# Schematic.net
KiCad netlist of a schematic drawn in Altium Designer
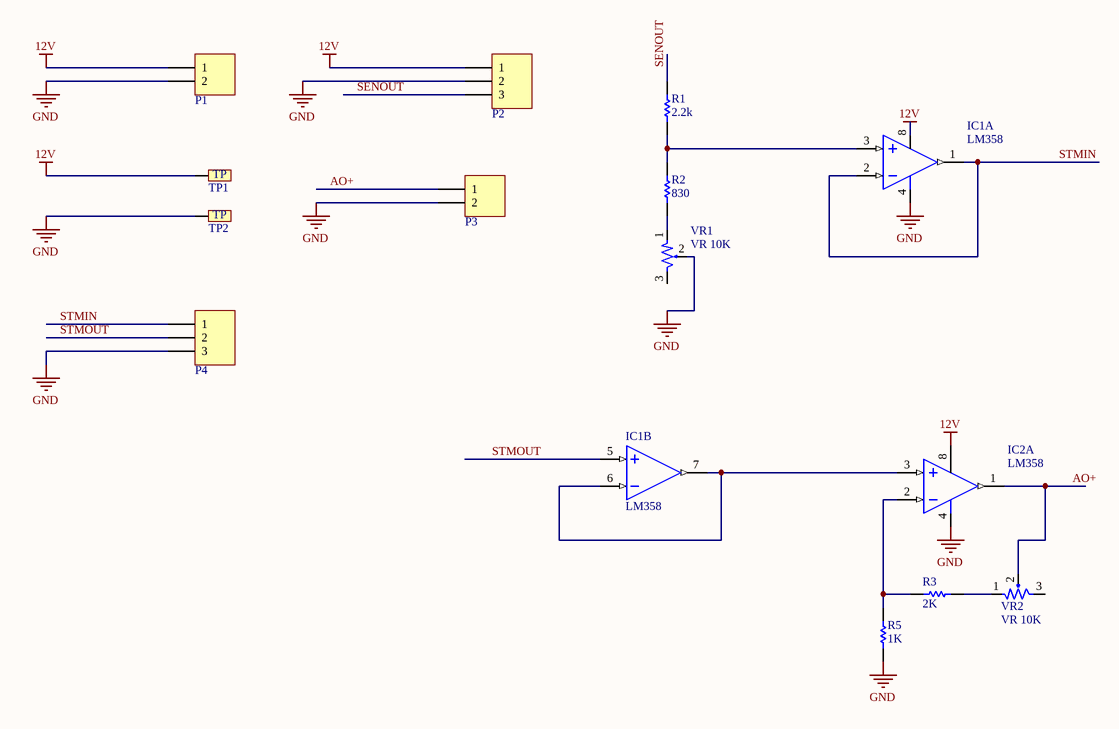
[diagram p0: Schematic.SchDoc]

(export (version "E")
  (design (tool "Eeschema 10.0.6"))
  (components
    (comp (ref "IC1")
      (value "LM358")
      (footprint "DIP8")
      (description "Low-Power Dual Operational Amplifier")
      (libsource (lib "LIBRARY") (part "LM358"))
    )
    (comp (ref "IC2")
      (value "LM358")
      (footprint "DIP8")
      (description "Low-Power Dual Operational Amplifier")
      (libsource (lib "LIBRARY") (part "LM358"))
    )
    (comp (ref "P1")
      (value "Header 2H")
      (footprint "JP2H")
      (description "Header, 2-Pin, Right Angle")
      (fields (field (name "PUBLISHER") "Altium Limited"))
      (libsource (lib "PIF_Library") (part "Header 2H"))
    )
    (comp (ref "P2")
      (value "Header 3")
      (footprint "JP3")
      (description "Header, 3-Pin")
      (fields (field (name "PUBLISHER") "Altium Limited"))
      (libsource (lib "PIF_Library") (part "Header 3"))
    )
    (comp (ref "P3")
      (value "Header 2H")
      (footprint "JP2H")
      (description "Header, 2-Pin, Right Angle")
      (fields (field (name "PUBLISHER") "Altium Limited"))
      (libsource (lib "PIF_Library") (part "Header 2H"))
    )
    (comp (ref "P4")
      (value "Header 3")
      (footprint "JP3")
      (description "Header, 3-Pin")
      (fields (field (name "PUBLISHER") "Altium Limited"))
      (libsource (lib "PIF_Library") (part "Header 3"))
    )
    (comp (ref "R1")
      (value "2.2k")
      (footprint "RES-SM-0805")
      (description "Resistor")
      (fields (field (name "Comment") "RESISTOR SMD"))
      (libsource (lib "PIF_Library") (part "RESISTOR SMD"))
    )
    (comp (ref "R2")
      (value "830")
      (footprint "RES-SM-0805")
      (description "Resistor")
      (fields (field (name "Comment") "RESISTOR SMD"))
      (libsource (lib "PIF_Library") (part "RESISTOR SMD"))
    )
    (comp (ref "R3")
      (value "2K")
      (footprint "RES-SM-0805")
      (description "Resistor")
      (fields (field (name "Comment") "RESISTOR SMD"))
      (libsource (lib "PIF_Library") (part "RESISTOR SMD"))
    )
    (comp (ref "R5")
      (value "1K")
      (footprint "RES-SM-0805")
      (description "Resistor")
      (fields (field (name "Comment") "RESISTOR SMD"))
      (libsource (lib "PIF_Library") (part "RESISTOR SMD"))
    )
    (comp (ref "TP1")
      (value "Test Point")
      (footprint "TP")
      (libsource (lib "PIF_Library") (part "Test Point"))
    )
    (comp (ref "TP2")
      (value "Test Point")
      (footprint "TP")
      (libsource (lib "PIF_Library") (part "Test Point"))
    )
    (comp (ref "VR1")
      (value "VR 10K")
      (footprint "Varistor 1")
      (description "Var Resistor")
      (fields (field (name "Comment") "10K"))
      (libsource (lib "PIF_Library") (part "Var Resistor"))
    )
    (comp (ref "VR2")
      (value "VR 10K")
      (footprint "Varistor 1")
      (description "Var Resistor")
      (fields (field (name "Comment") "10K"))
      (libsource (lib "PIF_Library") (part "Var Resistor"))
    )
  )
  (nets
    (net (code "1") (name "/AO+") (class "Default")
      (node (ref "IC2") (pin "1") (pinfunction "OUT_1") (pintype "output"))
      (node (ref "P3") (pin "1") (pinfunction "1_1") (pintype "passive"))
      (node (ref "VR2") (pin "2") (pinfunction "2_2") (pintype "passive"))
    )
    (net (code "2") (name "/SENOUT") (class "Default")
      (node (ref "P2") (pin "3") (pinfunction "3_3") (pintype "passive"))
      (node (ref "R1") (pin "2") (pinfunction "2_2") (pintype "passive"))
    )
    (net (code "3") (name "/STMIN") (class "Default")
      (node (ref "IC1") (pin "1") (pinfunction "OUT_1") (pintype "output"))
      (node (ref "IC1") (pin "2") (pinfunction "IN-_2") (pintype "input"))
      (node (ref "P4") (pin "1") (pinfunction "1_1") (pintype "passive"))
    )
    (net (code "4") (name "/STMOUT") (class "Default")
      (node (ref "IC1") (pin "5") (pinfunction "IN+_5") (pintype "input"))
      (node (ref "P4") (pin "2") (pinfunction "2_2") (pintype "passive"))
    )
    (net (code "5") (name "12V") (class "Default")
      (node (ref "IC1") (pin "8") (pinfunction "+V_8") (pintype "passive"))
      (node (ref "IC2") (pin "8") (pinfunction "+V_8") (pintype "passive"))
      (node (ref "P1") (pin "1") (pinfunction "1_1") (pintype "passive"))
      (node (ref "P2") (pin "1") (pinfunction "1_1") (pintype "passive"))
      (node (ref "TP1") (pin "TP1") (pinfunction "0_TP1") (pintype "passive"))
    )
    (net (code "6") (name "GND") (class "Default")
      (node (ref "IC1") (pin "4") (pinfunction "-V_4") (pintype "passive"))
      (node (ref "IC2") (pin "4") (pinfunction "-V_4") (pintype "passive"))
      (node (ref "P1") (pin "2") (pinfunction "2_2") (pintype "passive"))
      (node (ref "P2") (pin "2") (pinfunction "2_2") (pintype "passive"))
      (node (ref "P3") (pin "2") (pinfunction "2_2") (pintype "passive"))
      (node (ref "P4") (pin "3") (pinfunction "3_3") (pintype "passive"))
      (node (ref "R5") (pin "2") (pinfunction "2_2") (pintype "passive"))
      (node (ref "TP2") (pin "TP1") (pinfunction "0_TP1") (pintype "passive"))
      (node (ref "VR1") (pin "2") (pinfunction "2_2") (pintype "passive"))
    )
    (net (code "7") (name "Net-(IC1A-IN+)") (class "Default")
      (node (ref "IC1") (pin "3") (pinfunction "IN+_3") (pintype "input"))
      (node (ref "R1") (pin "1") (pinfunction "1_1") (pintype "passive"))
      (node (ref "R2") (pin "2") (pinfunction "2_2") (pintype "passive"))
    )
    (net (code "8") (name "Net-(IC1B-IN-)") (class "Default")
      (node (ref "IC1") (pin "6") (pinfunction "IN-_6") (pintype "input"))
      (node (ref "IC1") (pin "7") (pinfunction "OUT_7") (pintype "output"))
      (node (ref "IC2") (pin "3") (pinfunction "IN+_3") (pintype "input"))
    )
    (net (code "9") (name "Net-(IC2A-IN-)") (class "Default")
      (node (ref "IC2") (pin "2") (pinfunction "IN-_2") (pintype "input"))
      (node (ref "R3") (pin "2") (pinfunction "2_2") (pintype "passive"))
      (node (ref "R5") (pin "1") (pinfunction "1_1") (pintype "passive"))
    )
    (net (code "10") (name "Net-(R2-Pad1)") (class "Default")
      (node (ref "R2") (pin "1") (pinfunction "1_1") (pintype "passive"))
      (node (ref "VR1") (pin "1") (pinfunction "1_1") (pintype "passive"))
    )
    (net (code "11") (name "Net-(R3-Pad1)") (class "Default")
      (node (ref "R3") (pin "1") (pinfunction "1_1") (pintype "passive"))
      (node (ref "VR2") (pin "1") (pinfunction "1_1") (pintype "passive"))
    )
    (net (code "12") (name "unconnected-(VR1-Pad3)") (class "Default")
      (node (ref "VR1") (pin "3") (pinfunction "3_3") (pintype "passive"))
    )
    (net (code "13") (name "unconnected-(VR2-Pad3)") (class "Default")
      (node (ref "VR2") (pin "3") (pinfunction "3_3") (pintype "passive"))
    )
  )
)
